# total_project.net
KiCad netlist of a schematic drawn in Altium Designer
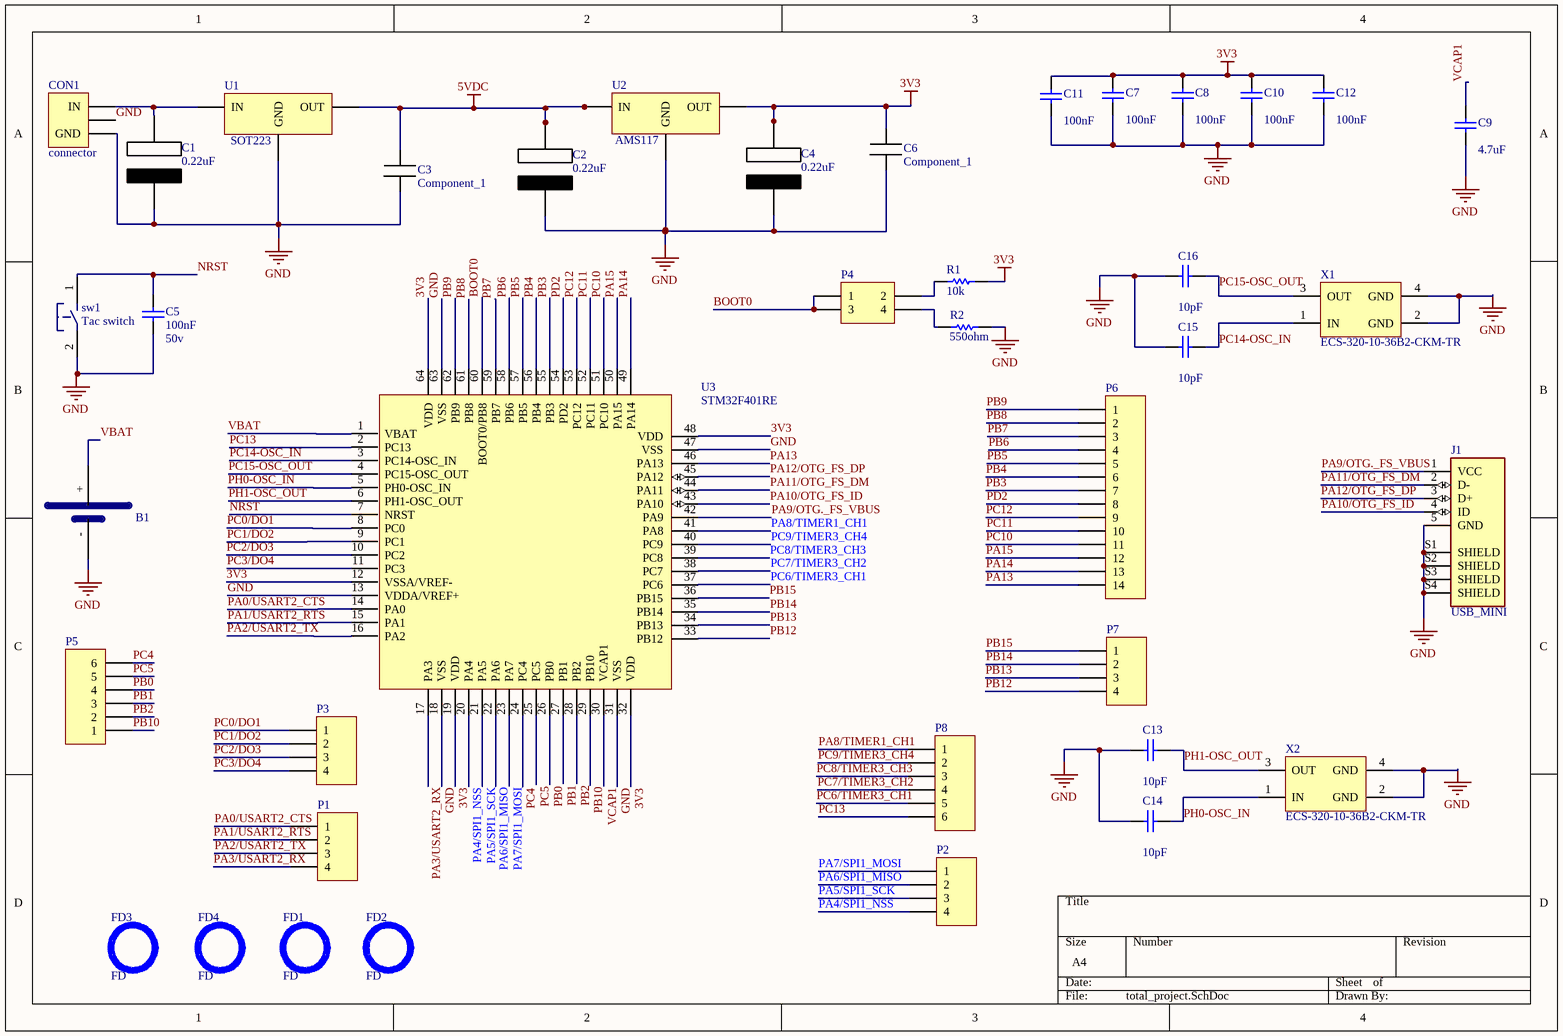
[diagram p0: total_project.SchDoc]

(export (version "E")
  (design (tool "Eeschema 10.0.6"))
  (components
    (comp (ref "B1")
      (value "Littium Battery")
      (footprint "MY_Battery")
      (description "3V PC Littium Battery")
      (fields (field (name "ASID PART NUMBER") "B-AS"))
      (libsource (lib "Mylib+Rev+4") (part "Battery"))
    )
    (comp (ref "C1")
      (value "0.22uF")
      (footprint "CAPCP3216X16N")
      (libsource (lib "tantalum capacitor") (part "Capasitor"))
    )
    (comp (ref "C2")
      (value "0.22uF")
      (footprint "CAPCP3216X16N")
      (libsource (lib "tantalum capacitor") (part "Capasitor"))
    )
    (comp (ref "C3")
      (value "Component_1")
      (footprint "CAPCP2407X01N")
      (libsource (lib "capasitor") (part "Component_1"))
    )
    (comp (ref "C4")
      (value "0.22uF")
      (footprint "CAPCP3216X16N")
      (libsource (lib "tantalum capacitor") (part "Capasitor"))
    )
    (comp (ref "C5")
      (value "100nF")
      (footprint "MY_0603")
      (description "None polar capacitor")
      (fields (field (name "ASID PART NUMBER") "C-AS") (field (name "VOLTE") "50v"))
      (libsource (lib "Mylib+Rev+4") (part "Cap ceramic"))
    )
    (comp (ref "C6")
      (value "Component_1")
      (footprint "CAPCP2407X01N")
      (libsource (lib "capasitor") (part "Component_1"))
    )
    (comp (ref "C7")
      (value "100nF")
      (footprint "1608[0603]cap")
      (description "Capacitor (Semiconductor SIM Model)")
      (fields (field (name "Comment") "Cap Semi_1") (field (name "PUBLISHER") "Altium Limited"))
      (libsource (lib "smartmcu") (part "Cap Semi_1"))
    )
    (comp (ref "C8")
      (value "100nF")
      (footprint "1608[0603]cap")
      (description "Capacitor (Semiconductor SIM Model)")
      (fields (field (name "Comment") "Cap Semi_1") (field (name "PUBLISHER") "Altium Limited"))
      (libsource (lib "smartmcu") (part "Cap Semi_1"))
    )
    (comp (ref "C9")
      (value "4.7uF")
      (footprint "1608[0603]cap")
      (description "Capacitor (Semiconductor SIM Model)")
      (fields (field (name "Comment") "Cap Semi_1") (field (name "PUBLISHER") "Altium Limited"))
      (libsource (lib "smartmcu") (part "Cap Semi_1_1"))
    )
    (comp (ref "C10")
      (value "100nF")
      (footprint "1608[0603]cap")
      (description "Capacitor (Semiconductor SIM Model)")
      (fields (field (name "Comment") "Cap Semi_1") (field (name "PUBLISHER") "Altium Limited"))
      (libsource (lib "smartmcu") (part "Cap Semi_1"))
    )
    (comp (ref "C11")
      (value "100nF")
      (footprint "1608[0603]cap")
      (description "Capacitor (Semiconductor SIM Model)")
      (fields (field (name "Comment") "Cap Semi_1") (field (name "PUBLISHER") "Altium Limited"))
      (libsource (lib "smartmcu") (part "Cap Semi_1"))
    )
    (comp (ref "C12")
      (value "100nF")
      (footprint "1608[0603]cap")
      (description "Capacitor (Semiconductor SIM Model)")
      (fields (field (name "Comment") "Cap Semi_1") (field (name "PUBLISHER") "Altium Limited"))
      (libsource (lib "smartmcu") (part "Cap Semi_1"))
    )
    (comp (ref "C13")
      (value "10pF")
      (footprint "0402cap")
      (description "Capacitor (Semiconductor SIM Model)")
      (fields (field (name "Comment") "Cap Semi_4") (field (name "PUBLISHER") "Altium Limited"))
      (libsource (lib "smartmcu") (part "Cap Semi_4"))
    )
    (comp (ref "C14")
      (value "10pF")
      (footprint "0402cap")
      (description "Capacitor (Semiconductor SIM Model)")
      (fields (field (name "Comment") "Cap Semi_4") (field (name "PUBLISHER") "Altium Limited"))
      (libsource (lib "smartmcu") (part "Cap Semi_4"))
    )
    (comp (ref "C15")
      (value "10pF")
      (footprint "0402cap")
      (description "Capacitor (Semiconductor SIM Model)")
      (fields (field (name "Comment") "Cap Semi_4") (field (name "PUBLISHER") "Altium Limited"))
      (libsource (lib "smartmcu") (part "Cap Semi_4"))
    )
    (comp (ref "C16")
      (value "10pF")
      (footprint "0402cap")
      (description "Capacitor (Semiconductor SIM Model)")
      (fields (field (name "Comment") "Cap Semi_4") (field (name "PUBLISHER") "Altium Limited"))
      (libsource (lib "smartmcu") (part "Cap Semi_4"))
    )
    (comp (ref "CON1")
      (value "connector")
      (footprint "connector")
      (libsource (lib "connector") (part "connector"))
    )
    (comp (ref "FD1") (value "FD") (footprint "FD") (libsource (lib "FD") (part "FD")))
    (comp (ref "FD2") (value "FD") (footprint "FD") (libsource (lib "FD") (part "FD")))
    (comp (ref "FD3") (value "FD") (footprint "FD") (libsource (lib "FD") (part "FD")))
    (comp (ref "FD4") (value "FD") (footprint "FD") (libsource (lib "FD") (part "FD")))
    (comp (ref "J1")
      (value "USB_MINI")
      (footprint "EDAC_690-005-299-043")
      (description "USB - mini B USB 2.0 Receptacle Connector 5 Position Surface Mount, Right Angle")
      (fields (field (name "MF") "EDAC Inc.") (field (name "MP") "690-005-299-043"))
      (libsource (lib "690-005-299-043") (part "690-005-299-043"))
    )
    (comp (ref "P1")
      (value "Header 4")
      (footprint "My_1X04")
      (description "Header, 4-Pin")
      (fields (field (name "ASID PART NUMBER") "Header 4-AS"))
      (libsource (lib "Mylib+Rev+4") (part "Header 4"))
    )
    (comp (ref "P2")
      (value "Header 4")
      (footprint "My_1X04")
      (description "Header, 4-Pin")
      (fields (field (name "ASID PART NUMBER") "Header 4-AS"))
      (libsource (lib "Mylib+Rev+4") (part "Header 4"))
    )
    (comp (ref "P3")
      (value "Header 4")
      (footprint "My_1X04")
      (description "Header, 4-Pin")
      (fields (field (name "ASID PART NUMBER") "Header 4-AS"))
      (libsource (lib "Mylib+Rev+4") (part "Header 4"))
    )
    (comp (ref "P4")
      (value "Header 2X2")
      (footprint "My_2X02")
      (description "Header, 2-Pin, Dual row")
      (fields (field (name "ASID PART NUMBER") "Header 2X2-AS"))
      (libsource (lib "Mylib+Rev+4") (part "Header 2X2"))
    )
    (comp (ref "P5")
      (value "Header 6")
      (footprint "My_1X06")
      (description "Header, 6-Pin")
      (fields (field (name "ASID PART NUMBER") "Header 6-AS"))
      (libsource (lib "") (part "Header 6_1"))
    )
    (comp (ref "P6")
      (value "Header 14")
      (footprint "My_1X14")
      (description "Header, 14-Pin")
      (fields (field (name "ASID PART NUMBER") "Header 14-AS"))
      (libsource (lib "Mylib+Rev+4") (part "Header 14"))
    )
    (comp (ref "P7")
      (value "Header 4")
      (footprint "My_1X04")
      (description "Header, 4-Pin")
      (fields (field (name "ASID PART NUMBER") "Header 4-AS"))
      (libsource (lib "Mylib+Rev+4") (part "Header 4"))
    )
    (comp (ref "P8")
      (value "Header 6")
      (footprint "My_1X06")
      (description "Header, 6-Pin")
      (fields (field (name "ASID PART NUMBER") "Header 6-AS"))
      (libsource (lib "Mylib+Rev+4") (part "Header 6"))
    )
    (comp (ref "R1")
      (value "10k")
      (footprint "MY_0805")
      (description "Standard resistor")
      (fields (field (name "ASID PART NUMBER") "Res-AS"))
      (libsource (lib "Mylib+Rev+4") (part "Res"))
    )
    (comp (ref "R2")
      (value "550ohm")
      (footprint "MY_0805")
      (description "Standard resistor")
      (fields (field (name "ASID PART NUMBER") "Res-AS"))
      (libsource (lib "Mylib+Rev+4") (part "Res"))
    )
    (comp (ref "sw1")
      (value "Tac switch")
      (footprint "MY_TACTILE-PTH")
      (description "small tac switch")
      (fields (field (name "ASID PART NUMBER") "Tac switch-AS"))
      (libsource (lib "Mylib+Rev+4") (part "Tac switch"))
    )
    (comp (ref "U1") (value "SOT223") (footprint "PCBComponent_1") (libsource (lib "LM340") (part "LM340")))
    (comp (ref "U2")
      (value "AMS117")
      (footprint "DPAK230P700X170-4N")
      (libsource (lib "AMS1117") (part "AMS1117"))
    )
    (comp (ref "U3")
      (value "STM32F401RE")
      (footprint "CQFP50P1200X1200X160-64N")
      (libsource (lib "stm32f401re") (part "STM32F401RE"))
    )
    (comp (ref "X1")
      (value "ECS-320-10-36B2-CKM-TR")
      (footprint "ECS-320-10-36B2-CKM-TR")
      (libsource (lib "ECS-320-10-36B2-CKM-TR") (part "ECS-320-10-36B2-CKM-TR"))
    )
    (comp (ref "X2")
      (value "ECS-320-10-36B2-CKM-TR")
      (footprint "ECS-320-10-36B2-CKM-TR")
      (libsource (lib "ECS-320-10-36B2-CKM-TR") (part "ECS-320-10-36B2-CKM-TR"))
    )
  )
  (nets
    (net (code "1") (name "/BOOT0") (class "Default")
      (node (ref "P4") (pin "1") (pinfunction "1_1") (pintype "passive"))
      (node (ref "P4") (pin "3") (pinfunction "3_3") (pintype "passive"))
      (node (ref "U3") (pin "60") (pinfunction "BOOT0/PB8_60") (pintype "power_in"))
    )
    (net (code "2") (name "/NRST") (class "Default")
      (node (ref "C5") (pin "2") (pinfunction "2_2") (pintype "passive"))
      (node (ref "U3") (pin "7") (pinfunction "NRST_7") (pintype "power_in"))
      (node (ref "sw1") (pin "1") (pinfunction "1_1") (pintype "passive"))
    )
    (net (code "3") (name "/PA0{slash}USART2_CTS") (class "Default")
      (node (ref "P1") (pin "1") (pinfunction "1_1") (pintype "passive"))
      (node (ref "U3") (pin "14") (pinfunction "PA0_14") (pintype "power_in"))
    )
    (net (code "4") (name "/PA1{slash}USART2_RTS") (class "Default")
      (node (ref "P1") (pin "2") (pinfunction "2_2") (pintype "passive"))
      (node (ref "U3") (pin "15") (pinfunction "PA1_15") (pintype "power_in"))
    )
    (net (code "5") (name "/PA2{slash}USART2_TX") (class "Default")
      (node (ref "P1") (pin "3") (pinfunction "3_3") (pintype "passive"))
      (node (ref "U3") (pin "16") (pinfunction "PA2_16") (pintype "power_in"))
    )
    (net (code "6") (name "/PA3{slash}USART2_RX") (class "Default")
      (node (ref "P1") (pin "4") (pinfunction "4_4") (pintype "passive"))
      (node (ref "U3") (pin "17") (pinfunction "PA3_17") (pintype "power_in"))
    )
    (net (code "7") (name "/PA4{slash}SPI1_NSS") (class "Default")
      (node (ref "P2") (pin "4") (pinfunction "4_4") (pintype "passive"))
      (node (ref "U3") (pin "20") (pinfunction "PA4_20") (pintype "power_in"))
    )
    (net (code "8") (name "/PA5{slash}SPI1_SCK") (class "Default")
      (node (ref "P2") (pin "3") (pinfunction "3_3") (pintype "passive"))
      (node (ref "U3") (pin "21") (pinfunction "PA5_21") (pintype "power_in"))
    )
    (net (code "9") (name "/PA6{slash}SPI1_MISO") (class "Default")
      (node (ref "P2") (pin "2") (pinfunction "2_2") (pintype "passive"))
      (node (ref "U3") (pin "22") (pinfunction "PA6_22") (pintype "power_in"))
    )
    (net (code "10") (name "/PA7{slash}SPI1_MOSI") (class "Default")
      (node (ref "P2") (pin "1") (pinfunction "1_1") (pintype "passive"))
      (node (ref "U3") (pin "23") (pinfunction "PA7_23") (pintype "power_in"))
    )
    (net (code "11") (name "/PA8{slash}TIMER1_CH1") (class "Default")
      (node (ref "P8") (pin "1") (pinfunction "1_1") (pintype "passive"))
      (node (ref "U3") (pin "41") (pinfunction "PA8_41") (pintype "power_in"))
    )
    (net (code "12") (name "/PA9{slash}OTG._FS_VBUS") (class "Default")
      (node (ref "J1") (pin "1") (pinfunction "VCC_1") (pintype "power_in"))
      (node (ref "U3") (pin "42") (pinfunction "PA9_42") (pintype "power_in"))
    )
    (net (code "13") (name "/PA10{slash}OTG_FS_ID") (class "Default")
      (node (ref "J1") (pin "4") (pinfunction "ID_4") (pintype "bidirectional"))
      (node (ref "U3") (pin "43") (pinfunction "PA10_43") (pintype "bidirectional"))
    )
    (net (code "14") (name "/PA11{slash}OTG_FS_DM") (class "Default")
      (node (ref "J1") (pin "2") (pinfunction "D-_2") (pintype "bidirectional"))
      (node (ref "U3") (pin "44") (pinfunction "PA11_44") (pintype "bidirectional"))
    )
    (net (code "15") (name "/PA12{slash}OTG_FS_DP") (class "Default")
      (node (ref "J1") (pin "3") (pinfunction "D+_3") (pintype "bidirectional"))
      (node (ref "U3") (pin "45") (pinfunction "PA12_45") (pintype "bidirectional"))
    )
    (net (code "16") (name "/PA13") (class "Default")
      (node (ref "P6") (pin "14") (pinfunction "14_14") (pintype "passive"))
      (node (ref "U3") (pin "46") (pinfunction "PA13_46") (pintype "power_in"))
    )
    (net (code "17") (name "/PA14") (class "Default")
      (node (ref "P6") (pin "13") (pinfunction "13_13") (pintype "passive"))
      (node (ref "U3") (pin "49") (pinfunction "PA14_49") (pintype "power_in"))
    )
    (net (code "18") (name "/PA15") (class "Default")
      (node (ref "P6") (pin "12") (pinfunction "12_12") (pintype "passive"))
      (node (ref "U3") (pin "50") (pinfunction "PA15_50") (pintype "power_in"))
    )
    (net (code "19") (name "/PB0") (class "Default")
      (node (ref "P5") (pin "4") (pinfunction "4_4") (pintype "passive"))
      (node (ref "U3") (pin "26") (pinfunction "PB0_26") (pintype "power_in"))
    )
    (net (code "20") (name "/PB1") (class "Default")
      (node (ref "P5") (pin "3") (pinfunction "3_3") (pintype "passive"))
      (node (ref "U3") (pin "27") (pinfunction "PB1_27") (pintype "power_in"))
    )
    (net (code "21") (name "/PB2") (class "Default")
      (node (ref "P5") (pin "2") (pinfunction "2_2") (pintype "passive"))
      (node (ref "U3") (pin "28") (pinfunction "PB2_28") (pintype "power_in"))
    )
    (net (code "22") (name "/PB3") (class "Default")
      (node (ref "P6") (pin "7") (pinfunction "7_7") (pintype "passive"))
      (node (ref "U3") (pin "55") (pinfunction "PB3_55") (pintype "power_in"))
    )
    (net (code "23") (name "/PB4") (class "Default")
      (node (ref "P6") (pin "6") (pinfunction "6_6") (pintype "passive"))
      (node (ref "U3") (pin "56") (pinfunction "PB4_56") (pintype "power_in"))
    )
    (net (code "24") (name "/PB5") (class "Default")
      (node (ref "P6") (pin "5") (pinfunction "5_5") (pintype "passive"))
      (node (ref "U3") (pin "57") (pinfunction "PB5_57") (pintype "power_in"))
    )
    (net (code "25") (name "/PB6") (class "Default")
      (node (ref "P6") (pin "4") (pinfunction "4_4") (pintype "passive"))
      (node (ref "U3") (pin "58") (pinfunction "PB6_58") (pintype "power_in"))
    )
    (net (code "26") (name "/PB7") (class "Default")
      (node (ref "P6") (pin "3") (pinfunction "3_3") (pintype "passive"))
      (node (ref "U3") (pin "59") (pinfunction "PB7_59") (pintype "power_in"))
    )
    (net (code "27") (name "/PB8") (class "Default")
      (node (ref "P6") (pin "2") (pinfunction "2_2") (pintype "passive"))
      (node (ref "U3") (pin "61") (pinfunction "PB8_61") (pintype "power_in"))
    )
    (net (code "28") (name "/PB9") (class "Default")
      (node (ref "P6") (pin "1") (pinfunction "1_1") (pintype "passive"))
      (node (ref "U3") (pin "62") (pinfunction "PB9_62") (pintype "power_in"))
    )
    (net (code "29") (name "/PB10") (class "Default")
      (node (ref "P5") (pin "1") (pinfunction "1_1") (pintype "passive"))
      (node (ref "U3") (pin "29") (pinfunction "PB10_29") (pintype "power_in"))
    )
    (net (code "30") (name "/PB12") (class "Default")
      (node (ref "P7") (pin "4") (pinfunction "4_4") (pintype "passive"))
      (node (ref "U3") (pin "33") (pinfunction "PB12_33") (pintype "power_in"))
    )
    (net (code "31") (name "/PB13") (class "Default")
      (node (ref "P7") (pin "3") (pinfunction "3_3") (pintype "passive"))
      (node (ref "U3") (pin "34") (pinfunction "PB13_34") (pintype "power_in"))
    )
    (net (code "32") (name "/PB14") (class "Default")
      (node (ref "P7") (pin "2") (pinfunction "2_2") (pintype "passive"))
      (node (ref "U3") (pin "35") (pinfunction "PB14_35") (pintype "power_in"))
    )
    (net (code "33") (name "/PB15") (class "Default")
      (node (ref "P7") (pin "1") (pinfunction "1_1") (pintype "passive"))
      (node (ref "U3") (pin "36") (pinfunction "PB15_36") (pintype "power_in"))
    )
    (net (code "34") (name "/PC0{slash}DO1") (class "Default")
      (node (ref "P3") (pin "1") (pinfunction "1_1") (pintype "passive"))
      (node (ref "U3") (pin "8") (pinfunction "PC0_8") (pintype "power_in"))
    )
    (net (code "35") (name "/PC1{slash}DO2") (class "Default")
      (node (ref "P3") (pin "2") (pinfunction "2_2") (pintype "passive"))
      (node (ref "U3") (pin "9") (pinfunction "PC1_9") (pintype "power_in"))
    )
    (net (code "36") (name "/PC2{slash}DO3") (class "Default")
      (node (ref "P3") (pin "3") (pinfunction "3_3") (pintype "passive"))
      (node (ref "U3") (pin "10") (pinfunction "PC2_10") (pintype "power_in"))
    )
    (net (code "37") (name "/PC3{slash}DO4") (class "Default")
      (node (ref "P3") (pin "4") (pinfunction "4_4") (pintype "passive"))
      (node (ref "U3") (pin "11") (pinfunction "PC3_11") (pintype "power_in"))
    )
    (net (code "38") (name "/PC4") (class "Default")
      (node (ref "P5") (pin "6") (pinfunction "6_6") (pintype "passive"))
      (node (ref "U3") (pin "24") (pinfunction "PC4_24") (pintype "power_in"))
    )
    (net (code "39") (name "/PC5") (class "Default")
      (node (ref "P5") (pin "5") (pinfunction "5_5") (pintype "passive"))
      (node (ref "U3") (pin "25") (pinfunction "PC5_25") (pintype "power_in"))
    )
    (net (code "40") (name "/PC6{slash}TIMER3_CH1") (class "Default")
      (node (ref "P8") (pin "5") (pinfunction "5_5") (pintype "passive"))
      (node (ref "U3") (pin "37") (pinfunction "PC6_37") (pintype "power_in"))
    )
    (net (code "41") (name "/PC7{slash}TIMER3_CH2") (class "Default")
      (node (ref "P8") (pin "4") (pinfunction "4_4") (pintype "passive"))
      (node (ref "U3") (pin "38") (pinfunction "PC7_38") (pintype "power_in"))
    )
    (net (code "42") (name "/PC8{slash}TIMER3_CH3") (class "Default")
      (node (ref "P8") (pin "3") (pinfunction "3_3") (pintype "passive"))
      (node (ref "U3") (pin "39") (pinfunction "PC8_39") (pintype "power_in"))
    )
    (net (code "43") (name "/PC9{slash}TIMER3_CH4") (class "Default")
      (node (ref "P8") (pin "2") (pinfunction "2_2") (pintype "passive"))
      (node (ref "U3") (pin "40") (pinfunction "PC9_40") (pintype "power_in"))
    )
    (net (code "44") (name "/PC10") (class "Default")
      (node (ref "P6") (pin "11") (pinfunction "11_11") (pintype "passive"))
      (node (ref "U3") (pin "51") (pinfunction "PC10_51") (pintype "power_in"))
    )
    (net (code "45") (name "/PC11") (class "Default")
      (node (ref "P6") (pin "10") (pinfunction "10_10") (pintype "passive"))
      (node (ref "U3") (pin "52") (pinfunction "PC11_52") (pintype "power_in"))
    )
    (net (code "46") (name "/PC12") (class "Default")
      (node (ref "P6") (pin "9") (pinfunction "9_9") (pintype "passive"))
      (node (ref "U3") (pin "53") (pinfunction "PC12_53") (pintype "power_in"))
    )
    (net (code "47") (name "/PC13") (class "Default")
      (node (ref "P8") (pin "6") (pinfunction "6_6") (pintype "passive"))
      (node (ref "U3") (pin "2") (pinfunction "PC13_2") (pintype "power_in"))
    )
    (net (code "48") (name "/PC14-OSC_IN") (class "Default")
      (node (ref "C15") (pin "2") (pinfunction "2_2") (pintype "passive"))
      (node (ref "U3") (pin "3") (pinfunction "PC14-OSC_IN_3") (pintype "power_in"))
      (node (ref "X1") (pin "1") (pinfunction "IN_1") (pintype "passive"))
    )
    (net (code "49") (name "/PC15-OSC_OUT") (class "Default")
      (node (ref "C16") (pin "2") (pinfunction "2_2") (pintype "passive"))
      (node (ref "U3") (pin "4") (pinfunction "PC15-OSC_OUT_4") (pintype "power_in"))
      (node (ref "X1") (pin "3") (pinfunction "OUT_3") (pintype "passive"))
    )
    (net (code "50") (name "/PD2") (class "Default")
      (node (ref "P6") (pin "8") (pinfunction "8_8") (pintype "passive"))
      (node (ref "U3") (pin "54") (pinfunction "PD2_54") (pintype "power_in"))
    )
    (net (code "51") (name "/PH0-OSC_IN") (class "Default")
      (node (ref "C14") (pin "2") (pinfunction "2_2") (pintype "passive"))
      (node (ref "U3") (pin "5") (pinfunction "PH0-OSC_IN_5") (pintype "power_in"))
      (node (ref "X2") (pin "1") (pinfunction "IN_1") (pintype "passive"))
    )
    (net (code "52") (name "/PH1-OSC_OUT") (class "Default")
      (node (ref "C13") (pin "2") (pinfunction "2_2") (pintype "passive"))
      (node (ref "U3") (pin "6") (pinfunction "PH1-OSC_OUT_6") (pintype "power_in"))
      (node (ref "X2") (pin "3") (pinfunction "OUT_3") (pintype "passive"))
    )
    (net (code "53") (name "/VBAT") (class "Default")
      (node (ref "B1") (pin "+") (pinfunction "+_+") (pintype "passive"))
      (node (ref "U3") (pin "1") (pinfunction "VBAT_1") (pintype "power_in"))
    )
    (net (code "54") (name "/VCAP1") (class "Default")
      (node (ref "C9") (pin "1") (pinfunction "1_1") (pintype "passive"))
      (node (ref "U3") (pin "30") (pinfunction "VCAP1_30") (pintype "power_in"))
    )
    (net (code "55") (name "3V3") (class "Default")
      (node (ref "C10") (pin "2") (pinfunction "2_2") (pintype "passive"))
      (node (ref "C11") (pin "2") (pinfunction "2_2") (pintype "passive"))
      (node (ref "C12") (pin "2") (pinfunction "2_2") (pintype "passive"))
      (node (ref "C4") (pin "2") (pinfunction "2_2") (pintype "passive"))
      (node (ref "C6") (pin "2") (pinfunction "2_2") (pintype "passive"))
      (node (ref "C7") (pin "2") (pinfunction "2_2") (pintype "passive"))
      (node (ref "C8") (pin "2") (pinfunction "2_2") (pintype "passive"))
      (node (ref "R1") (pin "2") (pinfunction "2_2") (pintype "passive"))
      (node (ref "U2") (pin "2") (pinfunction "OUT_2") (pintype "passive"))
      (node (ref "U3") (pin "12") (pinfunction "VSSA/VREF-_12") (pintype "power_in"))
      (node (ref "U3") (pin "19") (pinfunction "VDD_19") (pintype "power_in"))
      (node (ref "U3") (pin "32") (pinfunction "VDD_32") (pintype "power_in"))
      (node (ref "U3") (pin "48") (pinfunction "VDD_48") (pintype "power_in"))
      (node (ref "U3") (pin "64") (pinfunction "VDD_64") (pintype "power_in"))
    )
    (net (code "56") (name "5VDC") (class "Default")
      (node (ref "C2") (pin "2") (pinfunction "2_2") (pintype "passive"))
      (node (ref "C3") (pin "2") (pinfunction "2_2") (pintype "passive"))
      (node (ref "U1") (pin "3") (pinfunction "OUT_3") (pintype "passive"))
      (node (ref "U2") (pin "3") (pinfunction "IN_3") (pintype "passive"))
    )
    (net (code "57") (name "GND") (class "Default")
      (node (ref "B1") (pin "-") (pinfunction "-_-") (pintype "passive"))
      (node (ref "C1") (pin "1") (pinfunction "0_1") (pintype "passive"))
      (node (ref "C10") (pin "1") (pinfunction "1_1") (pintype "passive"))
      (node (ref "C11") (pin "1") (pinfunction "1_1") (pintype "passive"))
      (node (ref "C12") (pin "1") (pinfunction "1_1") (pintype "passive"))
      (node (ref "C13") (pin "1") (pinfunction "1_1") (pintype "passive"))
      (node (ref "C14") (pin "1") (pinfunction "1_1") (pintype "passive"))
      (node (ref "C15") (pin "1") (pinfunction "1_1") (pintype "passive"))
      (node (ref "C16") (pin "1") (pinfunction "1_1") (pintype "passive"))
      (node (ref "C2") (pin "1") (pinfunction "0_1") (pintype "passive"))
      (node (ref "C3") (pin "1") (pinfunction "1_1") (pintype "passive"))
      (node (ref "C4") (pin "1") (pinfunction "0_1") (pintype "passive"))
      (node (ref "C5") (pin "1") (pinfunction "1_1") (pintype "passive"))
      (node (ref "C6") (pin "1") (pinfunction "1_1") (pintype "passive"))
      (node (ref "C7") (pin "1") (pinfunction "1_1") (pintype "passive"))
      (node (ref "C8") (pin "1") (pinfunction "1_1") (pintype "passive"))
      (node (ref "C9") (pin "2") (pinfunction "2_2") (pintype "passive"))
      (node (ref "CON1") (pin "2") (pinfunction "GND_2") (pintype "passive"))
      (node (ref "CON1") (pin "3") (pinfunction "GND_3") (pintype "passive"))
      (node (ref "J1") (pin "5") (pinfunction "GND_5") (pintype "power_in"))
      (node (ref "J1") (pin "S1") (pinfunction "SHIELD_S1") (pintype "passive"))
      (node (ref "J1") (pin "S2") (pinfunction "SHIELD_S2") (pintype "passive"))
      (node (ref "J1") (pin "S3") (pinfunction "SHIELD_S3") (pintype "passive"))
      (node (ref "J1") (pin "S4") (pinfunction "SHIELD_S4") (pintype "passive"))
      (node (ref "R2") (pin "2") (pinfunction "2_2") (pintype "passive"))
      (node (ref "U1") (pin "2") (pinfunction "GND_2") (pintype "passive"))
      (node (ref "U2") (pin "1") (pinfunction "GND_1") (pintype "passive"))
      (node (ref "U3") (pin "13") (pinfunction "VDDA/VREF+_13") (pintype "power_in"))
      (node (ref "U3") (pin "18") (pinfunction "VSS_18") (pintype "power_in"))
      (node (ref "U3") (pin "31") (pinfunction "VSS_31") (pintype "power_in"))
      (node (ref "U3") (pin "47") (pinfunction "VSS_47") (pintype "power_in"))
      (node (ref "U3") (pin "63") (pinfunction "VSS_63") (pintype "power_in"))
      (node (ref "X1") (pin "2") (pinfunction "GND_2") (pintype "passive"))
      (node (ref "X1") (pin "4") (pinfunction "GND_4") (pintype "passive"))
      (node (ref "X2") (pin "2") (pinfunction "GND_2") (pintype "passive"))
      (node (ref "X2") (pin "4") (pinfunction "GND_4") (pintype "passive"))
      (node (ref "sw1") (pin "2") (pinfunction "2_2") (pintype "passive"))
    )
    (net (code "58") (name "Net-(CON1-IN)") (class "Default")
      (node (ref "C1") (pin "2") (pinfunction "2_2") (pintype "passive"))
      (node (ref "CON1") (pin "1") (pinfunction "IN_1") (pintype "passive"))
      (node (ref "U1") (pin "1") (pinfunction "IN_1") (pintype "passive"))
    )
    (net (code "59") (name "Net-(P4-Pad2)") (class "Default")
      (node (ref "P4") (pin "2") (pinfunction "2_2") (pintype "passive"))
      (node (ref "R1") (pin "1") (pinfunction "1_1") (pintype "passive"))
    )
    (net (code "60") (name "Net-(P4-Pad4)") (class "Default")
      (node (ref "P4") (pin "4") (pinfunction "4_4") (pintype "passive"))
      (node (ref "R2") (pin "1") (pinfunction "1_1") (pintype "passive"))
    )
  )
)
